# wifi_Shield_V1_0.net
KiCad netlist of a schematic drawn in EAGLE
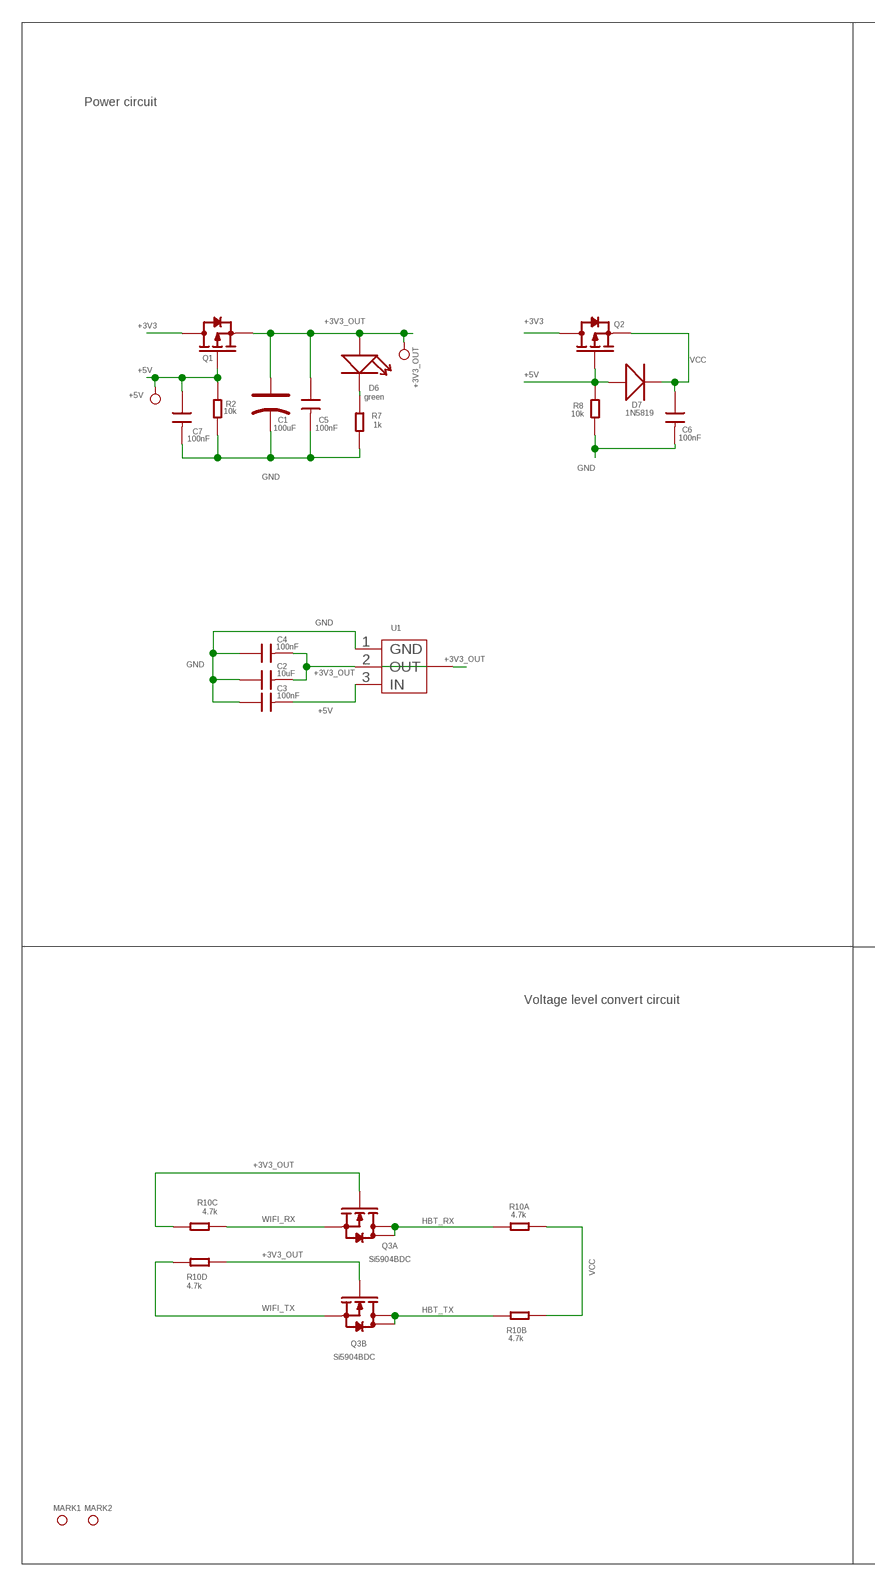
[diagram p0: schematic, sheet 1, part 1 of 2]
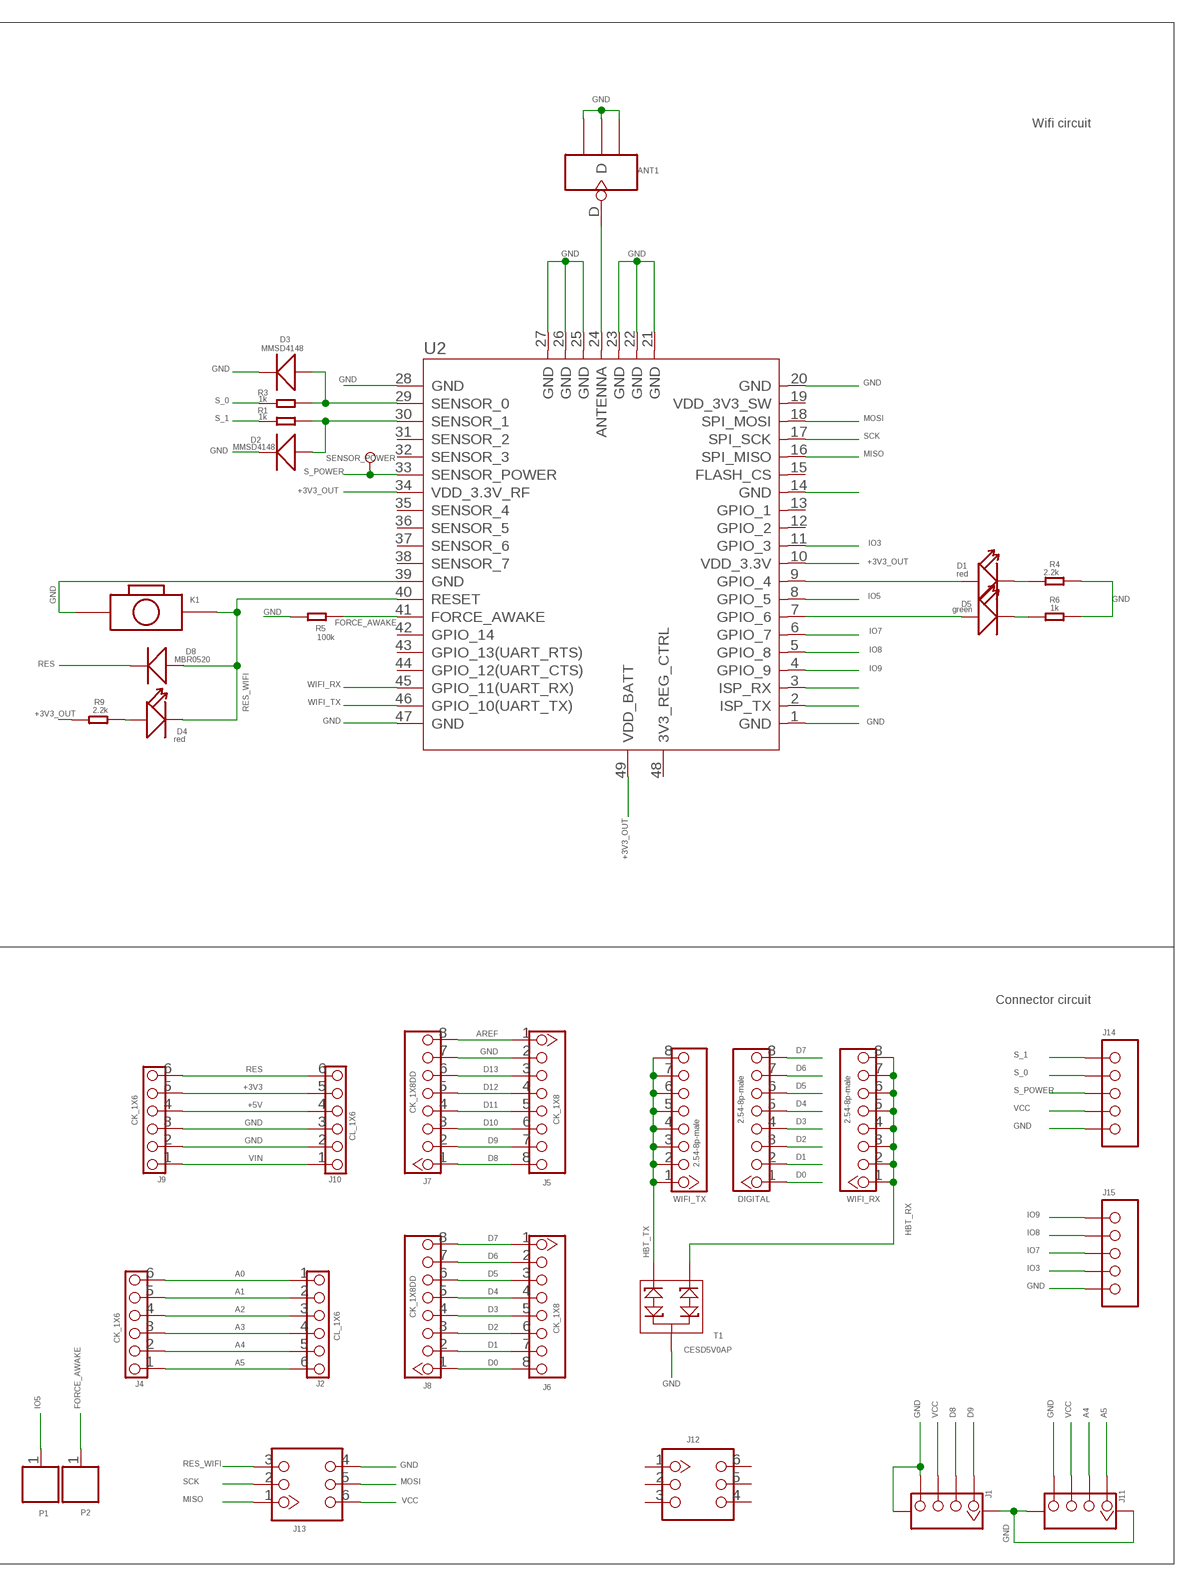
[diagram p1: schematic, sheet 1, part 2 of 2]

(export (version "E")
  (design (tool "Eeschema 10.0.6"))
  (components
    (comp (ref "+3V3_OUT")
      (value "PAD-TEST-POINT-CIRCLE_SIZE_3030")
      (footprint "eagle-import:TP_3535")
      (libsource (lib "eagle-import") (part "PAD-TEST-POINT-CIRCLE_SIZE_3030"))
    )
    (comp (ref "+5V")
      (value "PAD-TEST-POINT-CIRCLE_SIZE_3030")
      (footprint "eagle-import:TP_3535")
      (libsource (lib "eagle-import") (part "PAD-TEST-POINT-CIRCLE_SIZE_3030"))
    )
    (comp (ref "ANT1")
      (value "ANTENNA-U-FL")
      (footprint "eagle-import:4P-U-FL")
      (libsource (lib "eagle-import") (part "ANTENNA-U-FL"))
    )
    (comp (ref "C1")
      (value "100uF")
      (footprint "eagle-import:AVX-B")
      (libsource (lib "eagle-import") (part "CAP-AVX-B"))
    )
    (comp (ref "C2")
      (value "10uF")
      (footprint "eagle-import:0603")
      (libsource (lib "eagle-import") (part "C-0603"))
    )
    (comp (ref "C3")
      (value "100nF")
      (footprint "eagle-import:0603")
      (libsource (lib "eagle-import") (part "C-0603"))
    )
    (comp (ref "C4")
      (value "100nF")
      (footprint "eagle-import:0603")
      (libsource (lib "eagle-import") (part "C-0603"))
    )
    (comp (ref "C5")
      (value "100nF")
      (footprint "eagle-import:0603")
      (libsource (lib "eagle-import") (part "C-0603"))
    )
    (comp (ref "C6")
      (value "100nF")
      (footprint "eagle-import:0603")
      (libsource (lib "eagle-import") (part "C-0603"))
    )
    (comp (ref "C7")
      (value "100nF")
      (footprint "eagle-import:0603")
      (libsource (lib "eagle-import") (part "C-0603"))
    )
    (comp (ref "D1")
      (value "red")
      (footprint "eagle-import:LED-0603")
      (libsource (lib "eagle-import") (part "LED'0603'"))
    )
    (comp (ref "D2")
      (value "MMSD4148")
      (footprint "eagle-import:SOD123-2.7X1.6")
      (libsource (lib "eagle-import") (part "D-MBR0520LT1"))
    )
    (comp (ref "D3")
      (value "MMSD4148")
      (footprint "eagle-import:SOD123-2.7X1.6")
      (libsource (lib "eagle-import") (part "D-MBR0520LT1"))
    )
    (comp (ref "D4")
      (value "red")
      (footprint "eagle-import:LED-0603")
      (libsource (lib "eagle-import") (part "LED'0603'"))
    )
    (comp (ref "D5")
      (value "green")
      (footprint "eagle-import:LED-0603")
      (libsource (lib "eagle-import") (part "LED'0603'"))
    )
    (comp (ref "D6")
      (value "green")
      (footprint "eagle-import:LED-0603")
      (libsource (lib "eagle-import") (part "LED'0603'"))
    )
    (comp (ref "D7")
      (value "1N5819")
      (footprint "eagle-import:D2010")
      (libsource (lib "eagle-import") (part "D-SMA"))
    )
    (comp (ref "D8")
      (value "MBR0520")
      (footprint "eagle-import:SOD123-2.7X1.6")
      (libsource (lib "eagle-import") (part "D-MBR0520LT1"))
    )
    (comp (ref "DIGITAL")
      (value "2.54-8p-male")
      (footprint "eagle-import:8P-2.54")
      (libsource (lib "eagle-import") (part "HEADER-8P-2.54"))
    )
    (comp (ref "J1")
      (value "TWIG-4P-2.0-SMD-FEMALE-REINFORCE'90D'")
      (footprint "eagle-import:4P-SMD-2.0-90D")
      (libsource (lib "eagle-import") (part "TWIG-4P-2.0-SMD-FEMALE-REINFORCE'90D'"))
    )
    (comp (ref "J2")
      (value "CL_1X6")
      (footprint "eagle-import:6P-2.54-65_35MIL")
      (libsource (lib "eagle-import") (part "HEADER-6P-65/35MIL"))
    )
    (comp (ref "J4")
      (value "CK_1X6")
      (footprint "eagle-import:6P-2.54-65_35MIL")
      (libsource (lib "eagle-import") (part "HEADER-6P-65/35MIL"))
    )
    (comp (ref "J5")
      (value "CK_1X8")
      (footprint "eagle-import:8P-2.54")
      (libsource (lib "eagle-import") (part "HEADER-8P-2.54"))
    )
    (comp (ref "J6")
      (value "CK_1X8")
      (footprint "eagle-import:8P-2.54")
      (libsource (lib "eagle-import") (part "HEADER-8P-2.54"))
    )
    (comp (ref "J7")
      (value "CK_1X8DD")
      (footprint "eagle-import:8P-2.54")
      (libsource (lib "eagle-import") (part "HEADER-8P-2.54"))
    )
    (comp (ref "J8")
      (value "CK_1X8DD")
      (footprint "eagle-import:8P-2.54")
      (libsource (lib "eagle-import") (part "HEADER-8P-2.54"))
    )
    (comp (ref "J9")
      (value "CK_1X6")
      (footprint "eagle-import:6P-2.54-65_35MIL")
      (libsource (lib "eagle-import") (part "HEADER-6P-65/35MIL"))
    )
    (comp (ref "J10")
      (value "CL_1X6")
      (footprint "eagle-import:6P-2.54-65_35MIL")
      (libsource (lib "eagle-import") (part "HEADER-6P-65/35MIL"))
    )
    (comp (ref "J11")
      (value "TWIG-4P-2.0-SMD-FEMALE-REINFORCE'90D'")
      (footprint "eagle-import:4P-SMD-2.0-90D")
      (libsource (lib "eagle-import") (part "TWIG-4P-2.0-SMD-FEMALE-REINFORCE'90D'"))
    )
    (comp (ref "J12")
      (value "HEADER-2X3P-2.54")
      (footprint "eagle-import:2X3P-2.54")
      (libsource (lib "eagle-import") (part "HEADER-2X3P-2.54"))
    )
    (comp (ref "J13")
      (value "HEADER-2X3P-2.54")
      (footprint "eagle-import:2X3P-2.54")
      (libsource (lib "eagle-import") (part "HEADER-2X3P-2.54"))
    )
    (comp (ref "J14")
      (value "HEADER-5P-2.54")
      (footprint "eagle-import:5P-2.54")
      (libsource (lib "eagle-import") (part "HEADER-5P-2.54"))
    )
    (comp (ref "J15")
      (value "HEADER-5P-2.54")
      (footprint "eagle-import:5P-2.54")
      (libsource (lib "eagle-import") (part "HEADER-5P-2.54"))
    )
    (comp (ref "K1")
      (value "BOTTON-2P-90")
      (footprint "eagle-import:2P-7.62X3.56-90D")
      (libsource (lib "eagle-import") (part "BOTTON-2P-90"))
    )
    (comp (ref "MARK1")
      (value "PAD-MARK")
      (footprint "eagle-import:ROUND-MARK-0.635")
      (libsource (lib "eagle-import") (part "PAD-MARK"))
    )
    (comp (ref "MARK2")
      (value "PAD-MARK")
      (footprint "eagle-import:ROUND-MARK-0.635")
      (libsource (lib "eagle-import") (part "PAD-MARK"))
    )
    (comp (ref "P1")
      (value "PAD'60/30'")
      (footprint "eagle-import:1P-65_35MIL")
      (libsource (lib "eagle-import") (part "PAD'60/30'"))
    )
    (comp (ref "P2")
      (value "PAD'60/30'")
      (footprint "eagle-import:1P-65_35MIL")
      (libsource (lib "eagle-import") (part "PAD'60/30'"))
    )
    (comp (ref "Q1")
      (value "MOSFET-P'SI2323CDS/SI2305DS<BR>'")
      (footprint "eagle-import:SOT23")
      (libsource (lib "eagle-import") (part "MOSFET-P'SI2323CDS/SI2305DS{lt}BR{gt}'"))
    )
    (comp (ref "Q2")
      (value "MOSFET-P'SI2323CDS/SI2305DS<BR>'")
      (footprint "eagle-import:SOT23")
      (libsource (lib "eagle-import") (part "MOSFET-P'SI2323CDS/SI2305DS{lt}BR{gt}'"))
    )
    (comp (ref "Q3")
      (value "Si5904BDC")
      (footprint "eagle-import:1206-8")
      (libsource (lib "eagle-import") (part "010-DUAL-N-MOSFET_1206-8"))
    )
    (comp (ref "R1")
      (value "1k")
      (footprint "eagle-import:0603")
      (libsource (lib "eagle-import") (part "R-0603"))
    )
    (comp (ref "R2")
      (value "10k")
      (footprint "eagle-import:0603")
      (libsource (lib "eagle-import") (part "R-0603"))
    )
    (comp (ref "R3")
      (value "1k")
      (footprint "eagle-import:0603")
      (libsource (lib "eagle-import") (part "R-0603"))
    )
    (comp (ref "R4")
      (value "2.2k")
      (footprint "eagle-import:0603")
      (libsource (lib "eagle-import") (part "R-0603"))
    )
    (comp (ref "R5")
      (value "100k")
      (footprint "eagle-import:0603")
      (libsource (lib "eagle-import") (part "R-0603"))
    )
    (comp (ref "R6")
      (value "1k")
      (footprint "eagle-import:0603")
      (libsource (lib "eagle-import") (part "R-0603"))
    )
    (comp (ref "R7")
      (value "1k")
      (footprint "eagle-import:0603")
      (libsource (lib "eagle-import") (part "R-0603"))
    )
    (comp (ref "R8")
      (value "10k")
      (footprint "eagle-import:0603")
      (libsource (lib "eagle-import") (part "R-0603"))
    )
    (comp (ref "R9")
      (value "2.2k")
      (footprint "eagle-import:0603")
      (libsource (lib "eagle-import") (part "R-0603"))
    )
    (comp (ref "R10")
      (value "4.7k")
      (footprint "eagle-import:R1206-8")
      (libsource (lib "eagle-import") (part "005-4R_1206"))
    )
    (comp (ref "SENSOR_POWER")
      (value "PAD-TEST-POINT-CIRCLE_SIZE_3030")
      (footprint "eagle-import:TP_3535")
      (libsource (lib "eagle-import") (part "PAD-TEST-POINT-CIRCLE_SIZE_3030"))
    )
    (comp (ref "T1")
      (value "CESD5V0AP")
      (footprint "eagle-import:SOT23")
      (libsource (lib "eagle-import") (part "D-ESD-PESDXL2BT"))
    )
    (comp (ref "U1")
      (value "LD1117SOT89")
      (footprint "eagle-import:SOT89")
      (libsource (lib "eagle-import") (part "LD1117SOT89"))
    )
    (comp (ref "U2")
      (value "WIFI-RN-171")
      (footprint "eagle-import:49P-1.27-26.67X17.78")
      (libsource (lib "eagle-import") (part "WIFI-RN-171"))
    )
    (comp (ref "WIFI_RX")
      (value "2.54-8p-male")
      (footprint "eagle-import:8P-2.54")
      (libsource (lib "eagle-import") (part "HEADER-8P-2.54"))
    )
    (comp (ref "WIFI_TX")
      (value "2.54-8p-male")
      (footprint "eagle-import:8P-2.54")
      (libsource (lib "eagle-import") (part "HEADER-8P-2.54"))
    )
  )
  (nets
    (net (code "1") (name "/+3V3") (class "Default")
      (node (ref "J10") (pin "5") (pinfunction "5_5") (pintype "bidirectional"))
      (node (ref "J9") (pin "5") (pinfunction "5_5") (pintype "bidirectional"))
      (node (ref "Q1") (pin "3") (pinfunction "D_3") (pintype "passive"))
      (node (ref "Q2") (pin "3") (pinfunction "D_3") (pintype "passive"))
    )
    (net (code "2") (name "/+3V3_OUT") (class "Default")
      (node (ref "+3V3_OUT") (pin "T") (pinfunction "T_T") (pintype "bidirectional"))
      (node (ref "C1") (pin "+") (pinfunction "+_+") (pintype "passive"))
      (node (ref "C2") (pin "2") (pinfunction "2_2") (pintype "passive"))
      (node (ref "C4") (pin "2") (pinfunction "2_2") (pintype "passive"))
      (node (ref "C5") (pin "1") (pinfunction "1_1") (pintype "passive"))
      (node (ref "D6") (pin "+") (pinfunction "+_+") (pintype "passive"))
      (node (ref "Q1") (pin "2") (pinfunction "S_2") (pintype "passive"))
      (node (ref "Q3") (pin "2") (pinfunction "G_2") (pintype "passive"))
      (node (ref "Q3") (pin "4") (pinfunction "G_4") (pintype "passive"))
      (node (ref "R10") (pin "5") (pinfunction "2_5") (pintype "passive"))
      (node (ref "R10") (pin "6") (pinfunction "2_6") (pintype "passive"))
      (node (ref "R9") (pin "2") (pinfunction "2_2") (pintype "passive"))
      (node (ref "U1") (pin "2") (pinfunction "OUT_2") (pintype "bidirectional"))
      (node (ref "U1") (pin "4") (pinfunction "TAB_4") (pintype "bidirectional"))
      (node (ref "U2") (pin "10") (pinfunction "VDD_3.3V_10") (pintype "power_in"))
      (node (ref "U2") (pin "34") (pinfunction "VDD_3.3V_RF_34") (pintype "power_in"))
      (node (ref "U2") (pin "49") (pinfunction "VDD_BATT_49") (pintype "bidirectional"))
    )
    (net (code "3") (name "/+5V") (class "Default")
      (node (ref "+5V") (pin "T") (pinfunction "T_T") (pintype "bidirectional"))
      (node (ref "C3") (pin "2") (pinfunction "2_2") (pintype "passive"))
      (node (ref "C7") (pin "1") (pinfunction "1_1") (pintype "passive"))
      (node (ref "D7") (pin "+") (pinfunction "+_+") (pintype "passive"))
      (node (ref "J10") (pin "4") (pinfunction "4_4") (pintype "bidirectional"))
      (node (ref "J9") (pin "4") (pinfunction "4_4") (pintype "bidirectional"))
      (node (ref "Q1") (pin "1") (pinfunction "G_1") (pintype "passive"))
      (node (ref "Q2") (pin "1") (pinfunction "G_1") (pintype "passive"))
      (node (ref "R2") (pin "1") (pinfunction "1_1") (pintype "passive"))
      (node (ref "R8") (pin "1") (pinfunction "1_1") (pintype "passive"))
      (node (ref "U1") (pin "3") (pinfunction "IN_3") (pintype "bidirectional"))
    )
    (net (code "4") (name "/A0") (class "Default")
      (node (ref "J2") (pin "1") (pinfunction "1_1") (pintype "bidirectional"))
      (node (ref "J4") (pin "6") (pinfunction "6_6") (pintype "bidirectional"))
    )
    (net (code "5") (name "/A1") (class "Default")
      (node (ref "J2") (pin "2") (pinfunction "2_2") (pintype "bidirectional"))
      (node (ref "J4") (pin "5") (pinfunction "5_5") (pintype "bidirectional"))
    )
    (net (code "6") (name "/A2") (class "Default")
      (node (ref "J2") (pin "3") (pinfunction "3_3") (pintype "bidirectional"))
      (node (ref "J4") (pin "4") (pinfunction "4_4") (pintype "bidirectional"))
    )
    (net (code "7") (name "/A3") (class "Default")
      (node (ref "J2") (pin "4") (pinfunction "4_4") (pintype "bidirectional"))
      (node (ref "J4") (pin "3") (pinfunction "3_3") (pintype "bidirectional"))
    )
    (net (code "8") (name "/A4") (class "Default")
      (node (ref "J11") (pin "2") (pinfunction "2_2") (pintype "bidirectional"))
      (node (ref "J2") (pin "5") (pinfunction "5_5") (pintype "bidirectional"))
      (node (ref "J4") (pin "2") (pinfunction "2_2") (pintype "bidirectional"))
    )
    (net (code "9") (name "/A5") (class "Default")
      (node (ref "J11") (pin "1") (pinfunction "1_1") (pintype "bidirectional"))
      (node (ref "J2") (pin "6") (pinfunction "6_6") (pintype "bidirectional"))
      (node (ref "J4") (pin "1") (pinfunction "1_1") (pintype "bidirectional"))
    )
    (net (code "10") (name "/AREF") (class "Default")
      (node (ref "J5") (pin "1") (pinfunction "1_1") (pintype "bidirectional"))
      (node (ref "J7") (pin "8") (pinfunction "8_8") (pintype "bidirectional"))
    )
    (net (code "11") (name "/D0") (class "Default")
      (node (ref "DIGITAL") (pin "1") (pinfunction "1_1") (pintype "bidirectional"))
      (node (ref "J6") (pin "8") (pinfunction "8_8") (pintype "bidirectional"))
      (node (ref "J8") (pin "1") (pinfunction "1_1") (pintype "bidirectional"))
    )
    (net (code "12") (name "/D1") (class "Default")
      (node (ref "DIGITAL") (pin "2") (pinfunction "2_2") (pintype "bidirectional"))
      (node (ref "J6") (pin "7") (pinfunction "7_7") (pintype "bidirectional"))
      (node (ref "J8") (pin "2") (pinfunction "2_2") (pintype "bidirectional"))
    )
    (net (code "13") (name "/D2") (class "Default")
      (node (ref "DIGITAL") (pin "3") (pinfunction "3_3") (pintype "bidirectional"))
      (node (ref "J6") (pin "6") (pinfunction "6_6") (pintype "bidirectional"))
      (node (ref "J8") (pin "3") (pinfunction "3_3") (pintype "bidirectional"))
    )
    (net (code "14") (name "/D3") (class "Default")
      (node (ref "DIGITAL") (pin "4") (pinfunction "4_4") (pintype "bidirectional"))
      (node (ref "J6") (pin "5") (pinfunction "5_5") (pintype "bidirectional"))
      (node (ref "J8") (pin "4") (pinfunction "4_4") (pintype "bidirectional"))
    )
    (net (code "15") (name "/D4") (class "Default")
      (node (ref "DIGITAL") (pin "5") (pinfunction "5_5") (pintype "bidirectional"))
      (node (ref "J6") (pin "4") (pinfunction "4_4") (pintype "bidirectional"))
      (node (ref "J8") (pin "5") (pinfunction "5_5") (pintype "bidirectional"))
    )
    (net (code "16") (name "/D5") (class "Default")
      (node (ref "DIGITAL") (pin "6") (pinfunction "6_6") (pintype "bidirectional"))
      (node (ref "J6") (pin "3") (pinfunction "3_3") (pintype "bidirectional"))
      (node (ref "J8") (pin "6") (pinfunction "6_6") (pintype "bidirectional"))
    )
    (net (code "17") (name "/D6") (class "Default")
      (node (ref "DIGITAL") (pin "7") (pinfunction "7_7") (pintype "bidirectional"))
      (node (ref "J6") (pin "2") (pinfunction "2_2") (pintype "bidirectional"))
      (node (ref "J8") (pin "7") (pinfunction "7_7") (pintype "bidirectional"))
    )
    (net (code "18") (name "/D7") (class "Default")
      (node (ref "DIGITAL") (pin "8") (pinfunction "8_8") (pintype "bidirectional"))
      (node (ref "J6") (pin "1") (pinfunction "1_1") (pintype "bidirectional"))
      (node (ref "J8") (pin "8") (pinfunction "8_8") (pintype "bidirectional"))
    )
    (net (code "19") (name "/D8") (class "Default")
      (node (ref "J1") (pin "2") (pinfunction "2_2") (pintype "bidirectional"))
      (node (ref "J5") (pin "8") (pinfunction "8_8") (pintype "bidirectional"))
      (node (ref "J7") (pin "1") (pinfunction "1_1") (pintype "bidirectional"))
    )
    (net (code "20") (name "/D9") (class "Default")
      (node (ref "J1") (pin "1") (pinfunction "1_1") (pintype "bidirectional"))
      (node (ref "J5") (pin "7") (pinfunction "7_7") (pintype "bidirectional"))
      (node (ref "J7") (pin "2") (pinfunction "2_2") (pintype "bidirectional"))
    )
    (net (code "21") (name "/D10") (class "Default")
      (node (ref "J5") (pin "6") (pinfunction "6_6") (pintype "bidirectional"))
      (node (ref "J7") (pin "3") (pinfunction "3_3") (pintype "bidirectional"))
    )
    (net (code "22") (name "/D11") (class "Default")
      (node (ref "J5") (pin "5") (pinfunction "5_5") (pintype "bidirectional"))
      (node (ref "J7") (pin "4") (pinfunction "4_4") (pintype "bidirectional"))
    )
    (net (code "23") (name "/D12") (class "Default")
      (node (ref "J5") (pin "4") (pinfunction "4_4") (pintype "bidirectional"))
      (node (ref "J7") (pin "5") (pinfunction "5_5") (pintype "bidirectional"))
    )
    (net (code "24") (name "/D13") (class "Default")
      (node (ref "J5") (pin "3") (pinfunction "3_3") (pintype "bidirectional"))
      (node (ref "J7") (pin "6") (pinfunction "6_6") (pintype "bidirectional"))
    )
    (net (code "25") (name "/FORCE_AWAKE") (class "Default")
      (node (ref "P2") (pin "1") (pinfunction "P$1_1") (pintype "bidirectional"))
      (node (ref "R5") (pin "1") (pinfunction "1_1") (pintype "passive"))
      (node (ref "U2") (pin "41") (pinfunction "FORCE_AWAKE_41") (pintype "bidirectional"))
    )
    (net (code "26") (name "/GND") (class "Default")
      (node (ref "ANT1") (pin "GND1") (pinfunction "GND1_GND1") (pintype "bidirectional"))
      (node (ref "ANT1") (pin "GND2") (pinfunction "GND2_GND2") (pintype "bidirectional"))
      (node (ref "ANT1") (pin "GND3") (pinfunction "GND3_GND3") (pintype "bidirectional"))
      (node (ref "C1") (pin "-") (pinfunction "-_-") (pintype "passive"))
      (node (ref "C2") (pin "1") (pinfunction "1_1") (pintype "passive"))
      (node (ref "C3") (pin "1") (pinfunction "1_1") (pintype "passive"))
      (node (ref "C4") (pin "1") (pinfunction "1_1") (pintype "passive"))
      (node (ref "C5") (pin "2") (pinfunction "2_2") (pintype "passive"))
      (node (ref "C6") (pin "2") (pinfunction "2_2") (pintype "passive"))
      (node (ref "C7") (pin "2") (pinfunction "2_2") (pintype "passive"))
      (node (ref "D2") (pin "1") (pinfunction "-_1") (pintype "passive"))
      (node (ref "D3") (pin "1") (pinfunction "-_1") (pintype "passive"))
      (node (ref "J1") (pin "4") (pinfunction "4_4") (pintype "bidirectional"))
      (node (ref "J1") (pin "SS1") (pinfunction "SS1_SS1") (pintype "bidirectional"))
      (node (ref "J1") (pin "SS2") (pinfunction "SS2_SS2") (pintype "bidirectional"))
      (node (ref "J10") (pin "2") (pinfunction "2_2") (pintype "bidirectional"))
      (node (ref "J10") (pin "3") (pinfunction "3_3") (pintype "bidirectional"))
      (node (ref "J11") (pin "4") (pinfunction "4_4") (pintype "bidirectional"))
      (node (ref "J11") (pin "SS1") (pinfunction "SS1_SS1") (pintype "bidirectional"))
      (node (ref "J11") (pin "SS2") (pinfunction "SS2_SS2") (pintype "bidirectional"))
      (node (ref "J13") (pin "4") (pinfunction "4_4") (pintype "bidirectional"))
      (node (ref "J14") (pin "5") (pinfunction "5_5") (pintype "bidirectional"))
      (node (ref "J15") (pin "5") (pinfunction "5_5") (pintype "bidirectional"))
      (node (ref "J5") (pin "2") (pinfunction "2_2") (pintype "bidirectional"))
      (node (ref "J7") (pin "7") (pinfunction "7_7") (pintype "bidirectional"))
      (node (ref "J9") (pin "2") (pinfunction "2_2") (pintype "bidirectional"))
      (node (ref "J9") (pin "3") (pinfunction "3_3") (pintype "bidirectional"))
      (node (ref "K1") (pin "P$2") (pinfunction "2_P$2") (pintype "bidirectional"))
      (node (ref "R2") (pin "2") (pinfunction "2_2") (pintype "passive"))
      (node (ref "R4") (pin "1") (pinfunction "1_1") (pintype "passive"))
      (node (ref "R5") (pin "2") (pinfunction "2_2") (pintype "passive"))
      (node (ref "R6") (pin "1") (pinfunction "1_1") (pintype "passive"))
      (node (ref "R7") (pin "1") (pinfunction "1_1") (pintype "passive"))
      (node (ref "R8") (pin "2") (pinfunction "2_2") (pintype "passive"))
      (node (ref "T1") (pin "3") (pinfunction "3_3") (pintype "bidirectional"))
      (node (ref "U1") (pin "1") (pinfunction "GND_1") (pintype "bidirectional"))
      (node (ref "U2") (pin "1") (pinfunction "GND_1") (pintype "power_in"))
      (node (ref "U2") (pin "14") (pinfunction "GND_14") (pintype "power_in"))
      (node (ref "U2") (pin "20") (pinfunction "GND_20") (pintype "power_in"))
      (node (ref "U2") (pin "21") (pinfunction "GND_21") (pintype "power_in"))
      (node (ref "U2") (pin "22") (pinfunction "GND_22") (pintype "power_in"))
      (node (ref "U2") (pin "23") (pinfunction "GND_23") (pintype "power_in"))
      (node (ref "U2") (pin "25") (pinfunction "GND_25") (pintype "power_in"))
      (node (ref "U2") (pin "26") (pinfunction "GND_26") (pintype "power_in"))
      (node (ref "U2") (pin "27") (pinfunction "GND_27") (pintype "power_in"))
      (node (ref "U2") (pin "28") (pinfunction "GND_28") (pintype "power_in"))
      (node (ref "U2") (pin "39") (pinfunction "GND_39") (pintype "power_in"))
      (node (ref "U2") (pin "47") (pinfunction "GND_47") (pintype "power_in"))
    )
    (net (code "27") (name "/HBT_RX") (class "Default")
      (node (ref "Q3") (pin "7") (pinfunction "D_7") (pintype "passive"))
      (node (ref "Q3") (pin "8") (pinfunction "D_8") (pintype "passive"))
      (node (ref "R10") (pin "1") (pinfunction "1_1") (pintype "passive"))
      (node (ref "T1") (pin "1") (pinfunction "1_1") (pintype "power_in"))
      (node (ref "WIFI_RX") (pin "1") (pinfunction "1_1") (pintype "bidirectional"))
      (node (ref "WIFI_RX") (pin "2") (pinfunction "2_2") (pintype "bidirectional"))
      (node (ref "WIFI_RX") (pin "3") (pinfunction "3_3") (pintype "bidirectional"))
      (node (ref "WIFI_RX") (pin "4") (pinfunction "4_4") (pintype "bidirectional"))
      (node (ref "WIFI_RX") (pin "5") (pinfunction "5_5") (pintype "bidirectional"))
      (node (ref "WIFI_RX") (pin "6") (pinfunction "6_6") (pintype "bidirectional"))
      (node (ref "WIFI_RX") (pin "7") (pinfunction "7_7") (pintype "bidirectional"))
      (node (ref "WIFI_RX") (pin "8") (pinfunction "8_8") (pintype "bidirectional"))
    )
    (net (code "28") (name "/HBT_TX") (class "Default")
      (node (ref "Q3") (pin "5") (pinfunction "D_5") (pintype "passive"))
      (node (ref "Q3") (pin "6") (pinfunction "D_6") (pintype "passive"))
      (node (ref "R10") (pin "2") (pinfunction "1_2") (pintype "passive"))
      (node (ref "T1") (pin "2") (pinfunction "2_2") (pintype "power_in"))
      (node (ref "WIFI_TX") (pin "1") (pinfunction "1_1") (pintype "bidirectional"))
      (node (ref "WIFI_TX") (pin "2") (pinfunction "2_2") (pintype "bidirectional"))
      (node (ref "WIFI_TX") (pin "3") (pinfunction "3_3") (pintype "bidirectional"))
      (node (ref "WIFI_TX") (pin "4") (pinfunction "4_4") (pintype "bidirectional"))
      (node (ref "WIFI_TX") (pin "5") (pinfunction "5_5") (pintype "bidirectional"))
      (node (ref "WIFI_TX") (pin "6") (pinfunction "6_6") (pintype "bidirectional"))
      (node (ref "WIFI_TX") (pin "7") (pinfunction "7_7") (pintype "bidirectional"))
      (node (ref "WIFI_TX") (pin "8") (pinfunction "8_8") (pintype "bidirectional"))
    )
    (net (code "29") (name "/IO3") (class "Default")
      (node (ref "J15") (pin "4") (pinfunction "4_4") (pintype "bidirectional"))
      (node (ref "U2") (pin "11") (pinfunction "GPIO_3_11") (pintype "bidirectional"))
    )
    (net (code "30") (name "/IO5") (class "Default")
      (node (ref "P1") (pin "1") (pinfunction "P$1_1") (pintype "bidirectional"))
      (node (ref "U2") (pin "8") (pinfunction "GPIO_5_8") (pintype "bidirectional"))
    )
    (net (code "31") (name "/IO7") (class "Default")
      (node (ref "J15") (pin "3") (pinfunction "3_3") (pintype "bidirectional"))
      (node (ref "U2") (pin "6") (pinfunction "GPIO_7_6") (pintype "bidirectional"))
    )
    (net (code "32") (name "/IO8") (class "Default")
      (node (ref "J15") (pin "2") (pinfunction "2_2") (pintype "bidirectional"))
      (node (ref "U2") (pin "5") (pinfunction "GPIO_8_5") (pintype "bidirectional"))
    )
    (net (code "33") (name "/IO9") (class "Default")
      (node (ref "J15") (pin "1") (pinfunction "1_1") (pintype "bidirectional"))
      (node (ref "U2") (pin "4") (pinfunction "GPIO_9_4") (pintype "bidirectional"))
    )
    (net (code "34") (name "/MISO") (class "Default")
      (node (ref "J13") (pin "1") (pinfunction "1_1") (pintype "bidirectional"))
      (node (ref "U2") (pin "16") (pinfunction "SPI_MISO_16") (pintype "bidirectional"))
    )
    (net (code "35") (name "/MOSI") (class "Default")
      (node (ref "J13") (pin "5") (pinfunction "5_5") (pintype "bidirectional"))
      (node (ref "U2") (pin "18") (pinfunction "SPI_MOSI_18") (pintype "bidirectional"))
    )
    (net (code "36") (name "/RES") (class "Default")
      (node (ref "D8") (pin "1") (pinfunction "-_1") (pintype "passive"))
      (node (ref "J10") (pin "6") (pinfunction "6_6") (pintype "bidirectional"))
      (node (ref "J9") (pin "6") (pinfunction "6_6") (pintype "bidirectional"))
    )
    (net (code "37") (name "/RES_WIFI") (class "Default")
      (node (ref "D4") (pin "-") (pinfunction "-_-") (pintype "passive"))
      (node (ref "D8") (pin "2") (pinfunction "+_2") (pintype "passive"))
      (node (ref "J13") (pin "3") (pinfunction "3_3") (pintype "bidirectional"))
      (node (ref "K1") (pin "P$1") (pinfunction "1_P$1") (pintype "bidirectional"))
      (node (ref "U2") (pin "40") (pinfunction "RESET_40") (pintype "input"))
    )
    (net (code "38") (name "/SCK") (class "Default")
      (node (ref "J13") (pin "2") (pinfunction "2_2") (pintype "bidirectional"))
      (node (ref "U2") (pin "17") (pinfunction "SPI_SCK_17") (pintype "bidirectional"))
    )
    (net (code "39") (name "/S_0") (class "Default")
      (node (ref "J14") (pin "2") (pinfunction "2_2") (pintype "bidirectional"))
      (node (ref "R3") (pin "2") (pinfunction "2_2") (pintype "passive"))
    )
    (net (code "40") (name "/S_1") (class "Default")
      (node (ref "J14") (pin "1") (pinfunction "1_1") (pintype "bidirectional"))
      (node (ref "R1") (pin "2") (pinfunction "2_2") (pintype "passive"))
    )
    (net (code "41") (name "/S_POWER") (class "Default")
      (node (ref "J14") (pin "3") (pinfunction "3_3") (pintype "bidirectional"))
      (node (ref "SENSOR_POWER") (pin "T") (pinfunction "T_T") (pintype "bidirectional"))
      (node (ref "U2") (pin "33") (pinfunction "SENSOR_POWER_33") (pintype "output"))
    )
    (net (code "42") (name "/VCC") (class "Default")
      (node (ref "C6") (pin "1") (pinfunction "1_1") (pintype "passive"))
      (node (ref "D7") (pin "-") (pinfunction "-_-") (pintype "passive"))
      (node (ref "J1") (pin "3") (pinfunction "3_3") (pintype "bidirectional"))
      (node (ref "J11") (pin "3") (pinfunction "3_3") (pintype "bidirectional"))
      (node (ref "J13") (pin "6") (pinfunction "6_6") (pintype "bidirectional"))
      (node (ref "J14") (pin "4") (pinfunction "4_4") (pintype "bidirectional"))
      (node (ref "Q2") (pin "2") (pinfunction "S_2") (pintype "passive"))
      (node (ref "R10") (pin "7") (pinfunction "2_7") (pintype "passive"))
      (node (ref "R10") (pin "8") (pinfunction "2_8") (pintype "passive"))
    )
    (net (code "43") (name "/VIN") (class "Default")
      (node (ref "J10") (pin "1") (pinfunction "1_1") (pintype "bidirectional"))
      (node (ref "J9") (pin "1") (pinfunction "1_1") (pintype "bidirectional"))
    )
    (net (code "44") (name "/WIFI_RX") (class "Default")
      (node (ref "Q3") (pin "1") (pinfunction "S_1") (pintype "passive"))
      (node (ref "R10") (pin "3") (pinfunction "1_3") (pintype "passive"))
      (node (ref "U2") (pin "45") (pinfunction "GPIO_11(UART_RX)_45") (pintype "bidirectional"))
    )
    (net (code "45") (name "/WIFI_TX") (class "Default")
      (node (ref "Q3") (pin "3") (pinfunction "S_3") (pintype "passive"))
      (node (ref "R10") (pin "4") (pinfunction "1_4") (pintype "passive"))
      (node (ref "U2") (pin "46") (pinfunction "GPIO_10(UART_TX)_46") (pintype "bidirectional"))
    )
    (net (code "46") (name "Net-(D1-Pad-)") (class "Default")
      (node (ref "D1") (pin "-") (pinfunction "-_-") (pintype "passive"))
      (node (ref "R4") (pin "2") (pinfunction "2_2") (pintype "passive"))
    )
    (net (code "47") (name "Net-(D2-+)") (class "Default")
      (node (ref "D2") (pin "2") (pinfunction "+_2") (pintype "passive"))
      (node (ref "R1") (pin "1") (pinfunction "1_1") (pintype "passive"))
      (node (ref "U2") (pin "30") (pinfunction "SENSOR_1_30") (pintype "input"))
    )
    (net (code "48") (name "Net-(D3-+)") (class "Default")
      (node (ref "D3") (pin "2") (pinfunction "+_2") (pintype "passive"))
      (node (ref "R3") (pin "1") (pinfunction "1_1") (pintype "passive"))
      (node (ref "U2") (pin "29") (pinfunction "SENSOR_0_29") (pintype "input"))
    )
    (net (code "49") (name "Net-(D4-Pad+)") (class "Default")
      (node (ref "D4") (pin "+") (pinfunction "+_+") (pintype "passive"))
      (node (ref "R9") (pin "1") (pinfunction "1_1") (pintype "passive"))
    )
    (net (code "50") (name "Net-(D5-Pad-)") (class "Default")
      (node (ref "D5") (pin "-") (pinfunction "-_-") (pintype "passive"))
      (node (ref "R6") (pin "2") (pinfunction "2_2") (pintype "passive"))
    )
    (net (code "51") (name "Net-(D6-Pad-)") (class "Default")
      (node (ref "D6") (pin "-") (pinfunction "-_-") (pintype "passive"))
      (node (ref "R7") (pin "2") (pinfunction "2_2") (pintype "passive"))
    )
    (net (code "52") (name "Net-(U2-ANTENNA)") (class "Default")
      (node (ref "ANT1") (pin "D") (pinfunction "D_D") (pintype "bidirectional"))
      (node (ref "U2") (pin "24") (pinfunction "ANTENNA_24") (pintype "bidirectional"))
    )
    (net (code "53") (name "Net-(U2-GPIO_4)") (class "Default")
      (node (ref "D1") (pin "+") (pinfunction "+_+") (pintype "passive"))
      (node (ref "U2") (pin "9") (pinfunction "GPIO_4_9") (pintype "bidirectional"))
    )
    (net (code "54") (name "Net-(U2-GPIO_6)") (class "Default")
      (node (ref "D5") (pin "+") (pinfunction "+_+") (pintype "passive"))
      (node (ref "U2") (pin "7") (pinfunction "GPIO_6_7") (pintype "bidirectional"))
    )
    (net (code "55") (name "unconnected-(J12-Pad1)") (class "Default")
      (node (ref "J12") (pin "1") (pinfunction "1_1") (pintype "bidirectional"))
    )
    (net (code "56") (name "unconnected-(J12-Pad2)") (class "Default")
      (node (ref "J12") (pin "2") (pinfunction "2_2") (pintype "bidirectional"))
    )
    (net (code "57") (name "unconnected-(J12-Pad3)") (class "Default")
      (node (ref "J12") (pin "3") (pinfunction "3_3") (pintype "bidirectional"))
    )
    (net (code "58") (name "unconnected-(J12-Pad4)") (class "Default")
      (node (ref "J12") (pin "4") (pinfunction "4_4") (pintype "bidirectional"))
    )
    (net (code "59") (name "unconnected-(J12-Pad5)") (class "Default")
      (node (ref "J12") (pin "5") (pinfunction "5_5") (pintype "bidirectional"))
    )
    (net (code "60") (name "unconnected-(J12-Pad6)") (class "Default")
      (node (ref "J12") (pin "6") (pinfunction "6_6") (pintype "bidirectional"))
    )
    (net (code "61") (name "unconnected-(U2-3V3_REG_CTRL-Pad48)") (class "Default")
      (node (ref "U2") (pin "48") (pinfunction "3V3_REG_CTRL_48") (pintype "input"))
    )
    (net (code "62") (name "unconnected-(U2-FLASH_CS-Pad15)") (class "Default")
      (node (ref "U2") (pin "15") (pinfunction "FLASH_CS_15") (pintype "bidirectional"))
    )
    (net (code "63") (name "unconnected-(U2-GPIO_1-Pad13)") (class "Default")
      (node (ref "U2") (pin "13") (pinfunction "GPIO_1_13") (pintype "bidirectional"))
    )
    (net (code "64") (name "unconnected-(U2-GPIO_2-Pad12)") (class "Default")
      (node (ref "U2") (pin "12") (pinfunction "GPIO_2_12") (pintype "bidirectional"))
    )
    (net (code "65") (name "unconnected-(U2-GPIO_12(UART_CTS)-Pad44)") (class "Default")
      (node (ref "U2") (pin "44") (pinfunction "GPIO_12(UART_CTS)_44") (pintype "bidirectional"))
    )
    (net (code "66") (name "unconnected-(U2-GPIO_13(UART_RTS)-Pad43)") (class "Default")
      (node (ref "U2") (pin "43") (pinfunction "GPIO_13(UART_RTS)_43") (pintype "bidirectional"))
    )
    (net (code "67") (name "unconnected-(U2-GPIO_14-Pad42)") (class "Default")
      (node (ref "U2") (pin "42") (pinfunction "GPIO_14_42") (pintype "bidirectional"))
    )
    (net (code "68") (name "unconnected-(U2-ISP_RX-Pad3)") (class "Default")
      (node (ref "U2") (pin "3") (pinfunction "ISP_RX_3") (pintype "bidirectional"))
    )
    (net (code "69") (name "unconnected-(U2-ISP_TX-Pad2)") (class "Default")
      (node (ref "U2") (pin "2") (pinfunction "ISP_TX_2") (pintype "bidirectional"))
    )
    (net (code "70") (name "unconnected-(U2-SENSOR_2-Pad31)") (class "Default")
      (node (ref "U2") (pin "31") (pinfunction "SENSOR_2_31") (pintype "input"))
    )
    (net (code "71") (name "unconnected-(U2-SENSOR_3-Pad32)") (class "Default")
      (node (ref "U2") (pin "32") (pinfunction "SENSOR_3_32") (pintype "input"))
    )
    (net (code "72") (name "unconnected-(U2-SENSOR_4-Pad35)") (class "Default")
      (node (ref "U2") (pin "35") (pinfunction "SENSOR_4_35") (pintype "input"))
    )
    (net (code "73") (name "unconnected-(U2-SENSOR_5-Pad36)") (class "Default")
      (node (ref "U2") (pin "36") (pinfunction "SENSOR_5_36") (pintype "input"))
    )
    (net (code "74") (name "unconnected-(U2-SENSOR_6-Pad37)") (class "Default")
      (node (ref "U2") (pin "37") (pinfunction "SENSOR_6_37") (pintype "input"))
    )
    (net (code "75") (name "unconnected-(U2-SENSOR_7-Pad38)") (class "Default")
      (node (ref "U2") (pin "38") (pinfunction "SENSOR_7_38") (pintype "input"))
    )
    (net (code "76") (name "unconnected-(U2-VDD_3V3_SW-Pad19)") (class "Default")
      (node (ref "U2") (pin "19") (pinfunction "VDD_3V3_SW_19") (pintype "bidirectional"))
    )
  )
)
